# Christmas_Lights.net
KiCad netlist of a schematic drawn in EAGLE
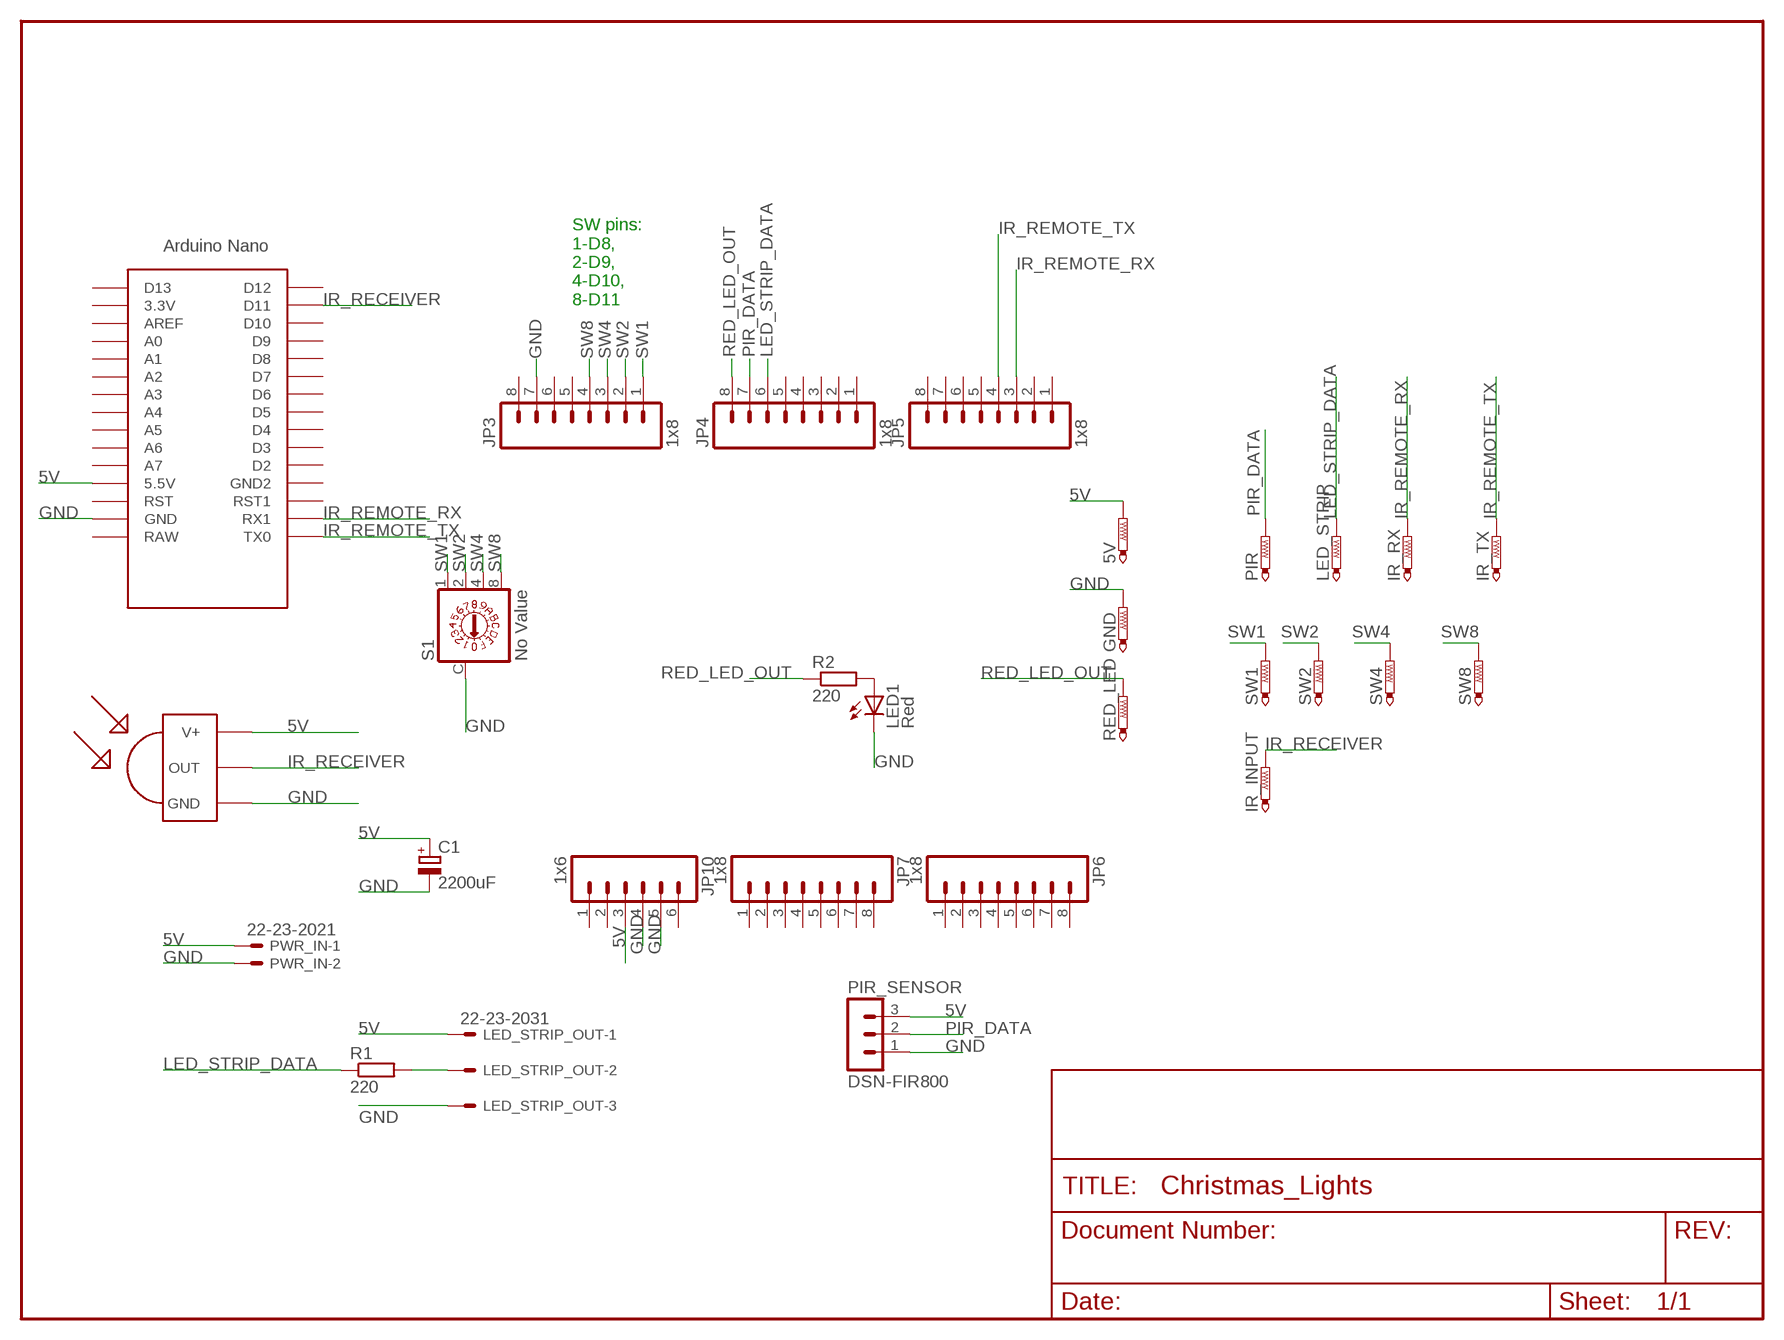
[diagram p0: schematic, sheet 1]

(export (version "E")
  (design (tool "Eeschema 10.0.6"))
  (components
    (comp (ref "5V")
      (value "PTR1PAD1-13")
      (footprint "eagle-import:P1-13")
      (libsource (lib "eagle-import") (part "PTR1PAD1-13"))
    )
    (comp (ref "C1")
      (value "2200uF")
      (footprint "eagle-import:E5-13")
      (libsource (lib "eagle-import") (part "CPOL-EUE5-13"))
    )
    (comp (ref "GND")
      (value "PTR1PAD1-13")
      (footprint "eagle-import:P1-13")
      (libsource (lib "eagle-import") (part "PTR1PAD1-13"))
    )
    (comp (ref "IR_INPUT")
      (value "PTR1PAD1-13")
      (footprint "eagle-import:P1-13")
      (libsource (lib "eagle-import") (part "PTR1PAD1-13"))
    )
    (comp (ref "IR_RX")
      (value "PTR1PAD1-13")
      (footprint "eagle-import:P1-13")
      (libsource (lib "eagle-import") (part "PTR1PAD1-13"))
    )
    (comp (ref "IR_TX")
      (value "PTR1PAD1-13")
      (footprint "eagle-import:P1-13")
      (libsource (lib "eagle-import") (part "PTR1PAD1-13"))
    )
    (comp (ref "JP3")
      (value "1x8")
      (footprint "eagle-import:1X08_LOCK")
      (libsource (lib "eagle-import") (part "M08LOCK"))
    )
    (comp (ref "JP4")
      (value "1x8")
      (footprint "eagle-import:1X08_LOCK")
      (libsource (lib "eagle-import") (part "M08LOCK"))
    )
    (comp (ref "JP5")
      (value "1x8")
      (footprint "eagle-import:1X08_LOCK")
      (libsource (lib "eagle-import") (part "M08LOCK"))
    )
    (comp (ref "JP6")
      (value "1x8")
      (footprint "eagle-import:1X08_LOCK")
      (libsource (lib "eagle-import") (part "M08LOCK"))
    )
    (comp (ref "JP7")
      (value "1x8")
      (footprint "eagle-import:1X08_LOCK")
      (libsource (lib "eagle-import") (part "M08LOCK"))
    )
    (comp (ref "JP10")
      (value "1x6")
      (footprint "eagle-import:1X06_LOCK")
      (libsource (lib "eagle-import") (part "M06LOCK"))
    )
    (comp (ref "LED1")
      (value "Red")
      (footprint "eagle-import:LED5MM")
      (libsource (lib "eagle-import") (part "LED5MM"))
    )
    (comp (ref "LED_STRIP")
      (value "PTR1PAD1-13")
      (footprint "eagle-import:P1-13")
      (libsource (lib "eagle-import") (part "PTR1PAD1-13"))
    )
    (comp (ref "LED_STRIP_OUT")
      (value "22-23-2031")
      (footprint "eagle-import:22-23-2031")
      (fields (field (name "MF") "MOLEX"))
      (libsource (lib "eagle-import") (part "22-23-2031"))
    )
    (comp (ref "PIR")
      (value "PTR1PAD1-13")
      (footprint "eagle-import:P1-13")
      (libsource (lib "eagle-import") (part "PTR1PAD1-13"))
    )
    (comp (ref "PIR_SENSOR")
      (value "DSN-FIR800")
      (footprint "eagle-import:MA03-1")
      (libsource (lib "eagle-import") (part "MA03-1"))
    )
    (comp (ref "PWR_IN")
      (value "22-23-2021")
      (footprint "eagle-import:22-23-2021")
      (fields (field (name "MF") "MOLEX"))
      (libsource (lib "eagle-import") (part "22-23-2021"))
    )
    (comp (ref "R1")
      (value "220")
      (footprint "eagle-import:0204_7")
      (libsource (lib "eagle-import") (part "R-EU_0204/7"))
    )
    (comp (ref "R2")
      (value "220")
      (footprint "eagle-import:0204_7")
      (libsource (lib "eagle-import") (part "R-EU_0204/7"))
    )
    (comp (ref "RED_LED")
      (value "PTR1PAD1-13")
      (footprint "eagle-import:P1-13")
      (libsource (lib "eagle-import") (part "PTR1PAD1-13"))
    )
    (comp (ref "S1")
      (value "No Value")
      (footprint "eagle-import:P103")
      (libsource (lib "eagle-import") (part "P103"))
    )
    (comp (ref "SW1")
      (value "PTR1PAD1-13")
      (footprint "eagle-import:P1-13")
      (libsource (lib "eagle-import") (part "PTR1PAD1-13"))
    )
    (comp (ref "SW2")
      (value "PTR1PAD1-13")
      (footprint "eagle-import:P1-13")
      (libsource (lib "eagle-import") (part "PTR1PAD1-13"))
    )
    (comp (ref "SW4")
      (value "PTR1PAD1-13")
      (footprint "eagle-import:P1-13")
      (libsource (lib "eagle-import") (part "PTR1PAD1-13"))
    )
    (comp (ref "SW8")
      (value "PTR1PAD1-13")
      (footprint "eagle-import:P1-13")
      (libsource (lib "eagle-import") (part "PTR1PAD1-13"))
    )
    (comp (ref "TSOP31328")
      (value "TSOP 31238")
      (footprint "eagle-import:TSOP17XX")
      (libsource (lib "eagle-import") (part "TSOP1730"))
    )
    (comp (ref "U$1")
      (value "NANO")
      (footprint "eagle-import:NANO")
      (libsource (lib "eagle-import") (part "NANO"))
    )
  )
  (nets
    (net (code "1") (name "/5V") (class "Default")
      (node (ref "5V") (pin "TP") (pinfunction "TP_TP") (pintype "input"))
      (node (ref "C1") (pin "+") (pinfunction "+_+") (pintype "passive"))
      (node (ref "JP10") (pin "3") (pinfunction "3_3") (pintype "passive"))
      (node (ref "LED_STRIP_OUT") (pin "1") (pinfunction "S_1") (pintype "passive"))
      (node (ref "PIR_SENSOR") (pin "3") (pinfunction "3_3") (pintype "passive"))
      (node (ref "PWR_IN") (pin "1") (pinfunction "S_1") (pintype "passive"))
      (node (ref "TSOP31328") (pin "V+") (pinfunction "V+_V+") (pintype "bidirectional"))
      (node (ref "U$1") (pin "5V") (pinfunction "5.5V_5V") (pintype "bidirectional"))
    )
    (net (code "2") (name "/GND") (class "Default")
      (node (ref "C1") (pin "-") (pinfunction "-_-") (pintype "passive"))
      (node (ref "GND") (pin "TP") (pinfunction "TP_TP") (pintype "input"))
      (node (ref "JP10") (pin "4") (pinfunction "4_4") (pintype "passive"))
      (node (ref "JP10") (pin "5") (pinfunction "5_5") (pintype "passive"))
      (node (ref "JP3") (pin "7") (pinfunction "7_7") (pintype "passive"))
      (node (ref "LED1") (pin "K") (pinfunction "C_K") (pintype "passive"))
      (node (ref "LED_STRIP_OUT") (pin "3") (pinfunction "S_3") (pintype "passive"))
      (node (ref "PIR_SENSOR") (pin "1") (pinfunction "1_1") (pintype "passive"))
      (node (ref "PWR_IN") (pin "2") (pinfunction "S_2") (pintype "passive"))
      (node (ref "S1") (pin "C") (pinfunction "C_C") (pintype "passive"))
      (node (ref "TSOP31328") (pin "GND") (pinfunction "GND_GND") (pintype "bidirectional"))
      (node (ref "U$1") (pin "GND") (pinfunction "GND_GND") (pintype "bidirectional"))
    )
    (net (code "3") (name "/IR_RECEIVER") (class "Default")
      (node (ref "IR_INPUT") (pin "TP") (pinfunction "TP_TP") (pintype "input"))
      (node (ref "TSOP31328") (pin "OUT") (pinfunction "OUT_OUT") (pintype "bidirectional"))
      (node (ref "U$1") (pin "D11") (pinfunction "D11_D11") (pintype "bidirectional"))
    )
    (net (code "4") (name "/IR_REMOTE_RX") (class "Default")
      (node (ref "IR_RX") (pin "TP") (pinfunction "TP_TP") (pintype "input"))
      (node (ref "JP5") (pin "3") (pinfunction "3_3") (pintype "passive"))
      (node (ref "U$1") (pin "RX1") (pinfunction "RX1_RX1") (pintype "bidirectional"))
    )
    (net (code "5") (name "/IR_REMOTE_TX") (class "Default")
      (node (ref "IR_TX") (pin "TP") (pinfunction "TP_TP") (pintype "input"))
      (node (ref "JP5") (pin "4") (pinfunction "4_4") (pintype "passive"))
      (node (ref "U$1") (pin "TX0") (pinfunction "TX0_TX0") (pintype "bidirectional"))
    )
    (net (code "6") (name "/LED_STRIP_DATA") (class "Default")
      (node (ref "JP4") (pin "6") (pinfunction "6_6") (pintype "passive"))
      (node (ref "LED_STRIP") (pin "TP") (pinfunction "TP_TP") (pintype "input"))
      (node (ref "R1") (pin "1") (pinfunction "1_1") (pintype "passive"))
    )
    (net (code "7") (name "/PIR_DATA") (class "Default")
      (node (ref "JP4") (pin "7") (pinfunction "7_7") (pintype "passive"))
      (node (ref "PIR") (pin "TP") (pinfunction "TP_TP") (pintype "input"))
      (node (ref "PIR_SENSOR") (pin "2") (pinfunction "2_2") (pintype "passive"))
    )
    (net (code "8") (name "/RED_LED_OUT") (class "Default")
      (node (ref "JP4") (pin "8") (pinfunction "8_8") (pintype "passive"))
      (node (ref "R2") (pin "1") (pinfunction "1_1") (pintype "passive"))
      (node (ref "RED_LED") (pin "TP") (pinfunction "TP_TP") (pintype "input"))
    )
    (net (code "9") (name "/SW1") (class "Default")
      (node (ref "JP3") (pin "1") (pinfunction "1_1") (pintype "passive"))
      (node (ref "S1") (pin "1") (pinfunction "1_1") (pintype "passive"))
      (node (ref "SW1") (pin "TP") (pinfunction "TP_TP") (pintype "input"))
    )
    (net (code "10") (name "/SW2") (class "Default")
      (node (ref "JP3") (pin "2") (pinfunction "2_2") (pintype "passive"))
      (node (ref "S1") (pin "2") (pinfunction "2_2") (pintype "passive"))
      (node (ref "SW2") (pin "TP") (pinfunction "TP_TP") (pintype "input"))
    )
    (net (code "11") (name "/SW4") (class "Default")
      (node (ref "JP3") (pin "3") (pinfunction "3_3") (pintype "passive"))
      (node (ref "S1") (pin "4") (pinfunction "4_4") (pintype "passive"))
      (node (ref "SW4") (pin "TP") (pinfunction "TP_TP") (pintype "input"))
    )
    (net (code "12") (name "/SW8") (class "Default")
      (node (ref "JP3") (pin "4") (pinfunction "4_4") (pintype "passive"))
      (node (ref "S1") (pin "8") (pinfunction "8_8") (pintype "passive"))
      (node (ref "SW8") (pin "TP") (pinfunction "TP_TP") (pintype "input"))
    )
    (net (code "13") (name "Net-(LED1-PadA)") (class "Default")
      (node (ref "LED1") (pin "A") (pinfunction "A_A") (pintype "passive"))
      (node (ref "R2") (pin "2") (pinfunction "2_2") (pintype "passive"))
    )
    (net (code "14") (name "Net-(LED_STRIP_OUTB-S)") (class "Default")
      (node (ref "LED_STRIP_OUT") (pin "2") (pinfunction "S_2") (pintype "passive"))
      (node (ref "R1") (pin "2") (pinfunction "2_2") (pintype "passive"))
    )
    (net (code "15") (name "unconnected-(JP3-Pad5)") (class "Default")
      (node (ref "JP3") (pin "5") (pinfunction "5_5") (pintype "passive"))
    )
    (net (code "16") (name "unconnected-(JP3-Pad6)") (class "Default")
      (node (ref "JP3") (pin "6") (pinfunction "6_6") (pintype "passive"))
    )
    (net (code "17") (name "unconnected-(JP3-Pad8)") (class "Default")
      (node (ref "JP3") (pin "8") (pinfunction "8_8") (pintype "passive"))
    )
    (net (code "18") (name "unconnected-(JP4-Pad1)") (class "Default")
      (node (ref "JP4") (pin "1") (pinfunction "1_1") (pintype "passive"))
    )
    (net (code "19") (name "unconnected-(JP4-Pad2)") (class "Default")
      (node (ref "JP4") (pin "2") (pinfunction "2_2") (pintype "passive"))
    )
    (net (code "20") (name "unconnected-(JP4-Pad3)") (class "Default")
      (node (ref "JP4") (pin "3") (pinfunction "3_3") (pintype "passive"))
    )
    (net (code "21") (name "unconnected-(JP4-Pad4)") (class "Default")
      (node (ref "JP4") (pin "4") (pinfunction "4_4") (pintype "passive"))
    )
    (net (code "22") (name "unconnected-(JP4-Pad5)") (class "Default")
      (node (ref "JP4") (pin "5") (pinfunction "5_5") (pintype "passive"))
    )
    (net (code "23") (name "unconnected-(JP5-Pad1)") (class "Default")
      (node (ref "JP5") (pin "1") (pinfunction "1_1") (pintype "passive"))
    )
    (net (code "24") (name "unconnected-(JP5-Pad2)") (class "Default")
      (node (ref "JP5") (pin "2") (pinfunction "2_2") (pintype "passive"))
    )
    (net (code "25") (name "unconnected-(JP5-Pad5)") (class "Default")
      (node (ref "JP5") (pin "5") (pinfunction "5_5") (pintype "passive"))
    )
    (net (code "26") (name "unconnected-(JP5-Pad6)") (class "Default")
      (node (ref "JP5") (pin "6") (pinfunction "6_6") (pintype "passive"))
    )
    (net (code "27") (name "unconnected-(JP5-Pad7)") (class "Default")
      (node (ref "JP5") (pin "7") (pinfunction "7_7") (pintype "passive"))
    )
    (net (code "28") (name "unconnected-(JP5-Pad8)") (class "Default")
      (node (ref "JP5") (pin "8") (pinfunction "8_8") (pintype "passive"))
    )
    (net (code "29") (name "unconnected-(JP6-Pad1)") (class "Default")
      (node (ref "JP6") (pin "1") (pinfunction "1_1") (pintype "passive"))
    )
    (net (code "30") (name "unconnected-(JP6-Pad2)") (class "Default")
      (node (ref "JP6") (pin "2") (pinfunction "2_2") (pintype "passive"))
    )
    (net (code "31") (name "unconnected-(JP6-Pad3)") (class "Default")
      (node (ref "JP6") (pin "3") (pinfunction "3_3") (pintype "passive"))
    )
    (net (code "32") (name "unconnected-(JP6-Pad4)") (class "Default")
      (node (ref "JP6") (pin "4") (pinfunction "4_4") (pintype "passive"))
    )
    (net (code "33") (name "unconnected-(JP6-Pad5)") (class "Default")
      (node (ref "JP6") (pin "5") (pinfunction "5_5") (pintype "passive"))
    )
    (net (code "34") (name "unconnected-(JP6-Pad6)") (class "Default")
      (node (ref "JP6") (pin "6") (pinfunction "6_6") (pintype "passive"))
    )
    (net (code "35") (name "unconnected-(JP6-Pad7)") (class "Default")
      (node (ref "JP6") (pin "7") (pinfunction "7_7") (pintype "passive"))
    )
    (net (code "36") (name "unconnected-(JP6-Pad8)") (class "Default")
      (node (ref "JP6") (pin "8") (pinfunction "8_8") (pintype "passive"))
    )
    (net (code "37") (name "unconnected-(JP7-Pad1)") (class "Default")
      (node (ref "JP7") (pin "1") (pinfunction "1_1") (pintype "passive"))
    )
    (net (code "38") (name "unconnected-(JP7-Pad2)") (class "Default")
      (node (ref "JP7") (pin "2") (pinfunction "2_2") (pintype "passive"))
    )
    (net (code "39") (name "unconnected-(JP7-Pad3)") (class "Default")
      (node (ref "JP7") (pin "3") (pinfunction "3_3") (pintype "passive"))
    )
    (net (code "40") (name "unconnected-(JP7-Pad4)") (class "Default")
      (node (ref "JP7") (pin "4") (pinfunction "4_4") (pintype "passive"))
    )
    (net (code "41") (name "unconnected-(JP7-Pad5)") (class "Default")
      (node (ref "JP7") (pin "5") (pinfunction "5_5") (pintype "passive"))
    )
    (net (code "42") (name "unconnected-(JP7-Pad6)") (class "Default")
      (node (ref "JP7") (pin "6") (pinfunction "6_6") (pintype "passive"))
    )
    (net (code "43") (name "unconnected-(JP7-Pad7)") (class "Default")
      (node (ref "JP7") (pin "7") (pinfunction "7_7") (pintype "passive"))
    )
    (net (code "44") (name "unconnected-(JP7-Pad8)") (class "Default")
      (node (ref "JP7") (pin "8") (pinfunction "8_8") (pintype "passive"))
    )
    (net (code "45") (name "unconnected-(JP10-Pad1)") (class "Default")
      (node (ref "JP10") (pin "1") (pinfunction "1_1") (pintype "passive"))
    )
    (net (code "46") (name "unconnected-(JP10-Pad2)") (class "Default")
      (node (ref "JP10") (pin "2") (pinfunction "2_2") (pintype "passive"))
    )
    (net (code "47") (name "unconnected-(JP10-Pad6)") (class "Default")
      (node (ref "JP10") (pin "6") (pinfunction "6_6") (pintype "passive"))
    )
    (net (code "48") (name "unconnected-(U$1-GND2-PadGND1)") (class "Default")
      (node (ref "U$1") (pin "GND1") (pinfunction "GND2_GND1") (pintype "bidirectional"))
    )
    (net (code "49") (name "unconnected-(U$1-Pad3.3V)") (class "Default")
      (node (ref "U$1") (pin "3.3V") (pinfunction "3.3V_3.3V") (pintype "bidirectional"))
    )
    (net (code "50") (name "unconnected-(U$1-PadA0)") (class "Default")
      (node (ref "U$1") (pin "A0") (pinfunction "A0_A0") (pintype "bidirectional"))
    )
    (net (code "51") (name "unconnected-(U$1-PadA1)") (class "Default")
      (node (ref "U$1") (pin "A1") (pinfunction "A1_A1") (pintype "bidirectional"))
    )
    (net (code "52") (name "unconnected-(U$1-PadA2)") (class "Default")
      (node (ref "U$1") (pin "A2") (pinfunction "A2_A2") (pintype "bidirectional"))
    )
    (net (code "53") (name "unconnected-(U$1-PadA3)") (class "Default")
      (node (ref "U$1") (pin "A3") (pinfunction "A3_A3") (pintype "bidirectional"))
    )
    (net (code "54") (name "unconnected-(U$1-PadA4)") (class "Default")
      (node (ref "U$1") (pin "A4") (pinfunction "A4_A4") (pintype "bidirectional"))
    )
    (net (code "55") (name "unconnected-(U$1-PadA5)") (class "Default")
      (node (ref "U$1") (pin "A5") (pinfunction "A5_A5") (pintype "bidirectional"))
    )
    (net (code "56") (name "unconnected-(U$1-PadA6)") (class "Default")
      (node (ref "U$1") (pin "A6") (pinfunction "A6_A6") (pintype "bidirectional"))
    )
    (net (code "57") (name "unconnected-(U$1-PadA7)") (class "Default")
      (node (ref "U$1") (pin "A7") (pinfunction "A7_A7") (pintype "bidirectional"))
    )
    (net (code "58") (name "unconnected-(U$1-PadAREF)") (class "Default")
      (node (ref "U$1") (pin "AREF") (pinfunction "AREF_AREF") (pintype "bidirectional"))
    )
    (net (code "59") (name "unconnected-(U$1-PadD2)") (class "Default")
      (node (ref "U$1") (pin "D2") (pinfunction "D2_D2") (pintype "bidirectional"))
    )
    (net (code "60") (name "unconnected-(U$1-PadD3)") (class "Default")
      (node (ref "U$1") (pin "D3") (pinfunction "D3_D3") (pintype "bidirectional"))
    )
    (net (code "61") (name "unconnected-(U$1-PadD4)") (class "Default")
      (node (ref "U$1") (pin "D4") (pinfunction "D4_D4") (pintype "bidirectional"))
    )
    (net (code "62") (name "unconnected-(U$1-PadD5)") (class "Default")
      (node (ref "U$1") (pin "D5") (pinfunction "D5_D5") (pintype "bidirectional"))
    )
    (net (code "63") (name "unconnected-(U$1-PadD6)") (class "Default")
      (node (ref "U$1") (pin "D6") (pinfunction "D6_D6") (pintype "bidirectional"))
    )
    (net (code "64") (name "unconnected-(U$1-PadD7)") (class "Default")
      (node (ref "U$1") (pin "D7") (pinfunction "D7_D7") (pintype "bidirectional"))
    )
    (net (code "65") (name "unconnected-(U$1-PadD8)") (class "Default")
      (node (ref "U$1") (pin "D8") (pinfunction "D8_D8") (pintype "bidirectional"))
    )
    (net (code "66") (name "unconnected-(U$1-PadD9)") (class "Default")
      (node (ref "U$1") (pin "D9") (pinfunction "D9_D9") (pintype "bidirectional"))
    )
    (net (code "67") (name "unconnected-(U$1-PadD10)") (class "Default")
      (node (ref "U$1") (pin "D10") (pinfunction "D10_D10") (pintype "bidirectional"))
    )
    (net (code "68") (name "unconnected-(U$1-PadD12)") (class "Default")
      (node (ref "U$1") (pin "D12") (pinfunction "D12_D12") (pintype "bidirectional"))
    )
    (net (code "69") (name "unconnected-(U$1-PadD13)") (class "Default")
      (node (ref "U$1") (pin "D13") (pinfunction "D13_D13") (pintype "bidirectional"))
    )
    (net (code "70") (name "unconnected-(U$1-PadICSP1)") (class "Default")
      (node (ref "U$1") (pin "ICSP1") (pinfunction "ICSP1_ICSP1") (pintype "bidirectional"))
    )
    (net (code "71") (name "unconnected-(U$1-PadICSP2)") (class "Default")
      (node (ref "U$1") (pin "ICSP2") (pinfunction "ICSP2_ICSP2") (pintype "bidirectional"))
    )
    (net (code "72") (name "unconnected-(U$1-PadICSP3)") (class "Default")
      (node (ref "U$1") (pin "ICSP3") (pinfunction "ICSP3_ICSP3") (pintype "bidirectional"))
    )
    (net (code "73") (name "unconnected-(U$1-PadICSP4)") (class "Default")
      (node (ref "U$1") (pin "ICSP4") (pinfunction "ICSP4_ICSP4") (pintype "bidirectional"))
    )
    (net (code "74") (name "unconnected-(U$1-PadICSP5)") (class "Default")
      (node (ref "U$1") (pin "ICSP5") (pinfunction "ICSP5_ICSP5") (pintype "bidirectional"))
    )
    (net (code "75") (name "unconnected-(U$1-PadICSP6)") (class "Default")
      (node (ref "U$1") (pin "ICSP6") (pinfunction "ICSP6_ICSP6") (pintype "bidirectional"))
    )
    (net (code "76") (name "unconnected-(U$1-PadRAW)") (class "Default")
      (node (ref "U$1") (pin "RAW") (pinfunction "RAW_RAW") (pintype "bidirectional"))
    )
    (net (code "77") (name "unconnected-(U$1-PadRST)") (class "Default")
      (node (ref "U$1") (pin "RST") (pinfunction "RST_RST") (pintype "bidirectional"))
    )
    (net (code "78") (name "unconnected-(U$1-PadRST1)") (class "Default")
      (node (ref "U$1") (pin "RST1") (pinfunction "RST1_RST1") (pintype "bidirectional"))
    )
  )
)
